# motherboard.net
KiCad netlist of a schematic drawn in EAGLE
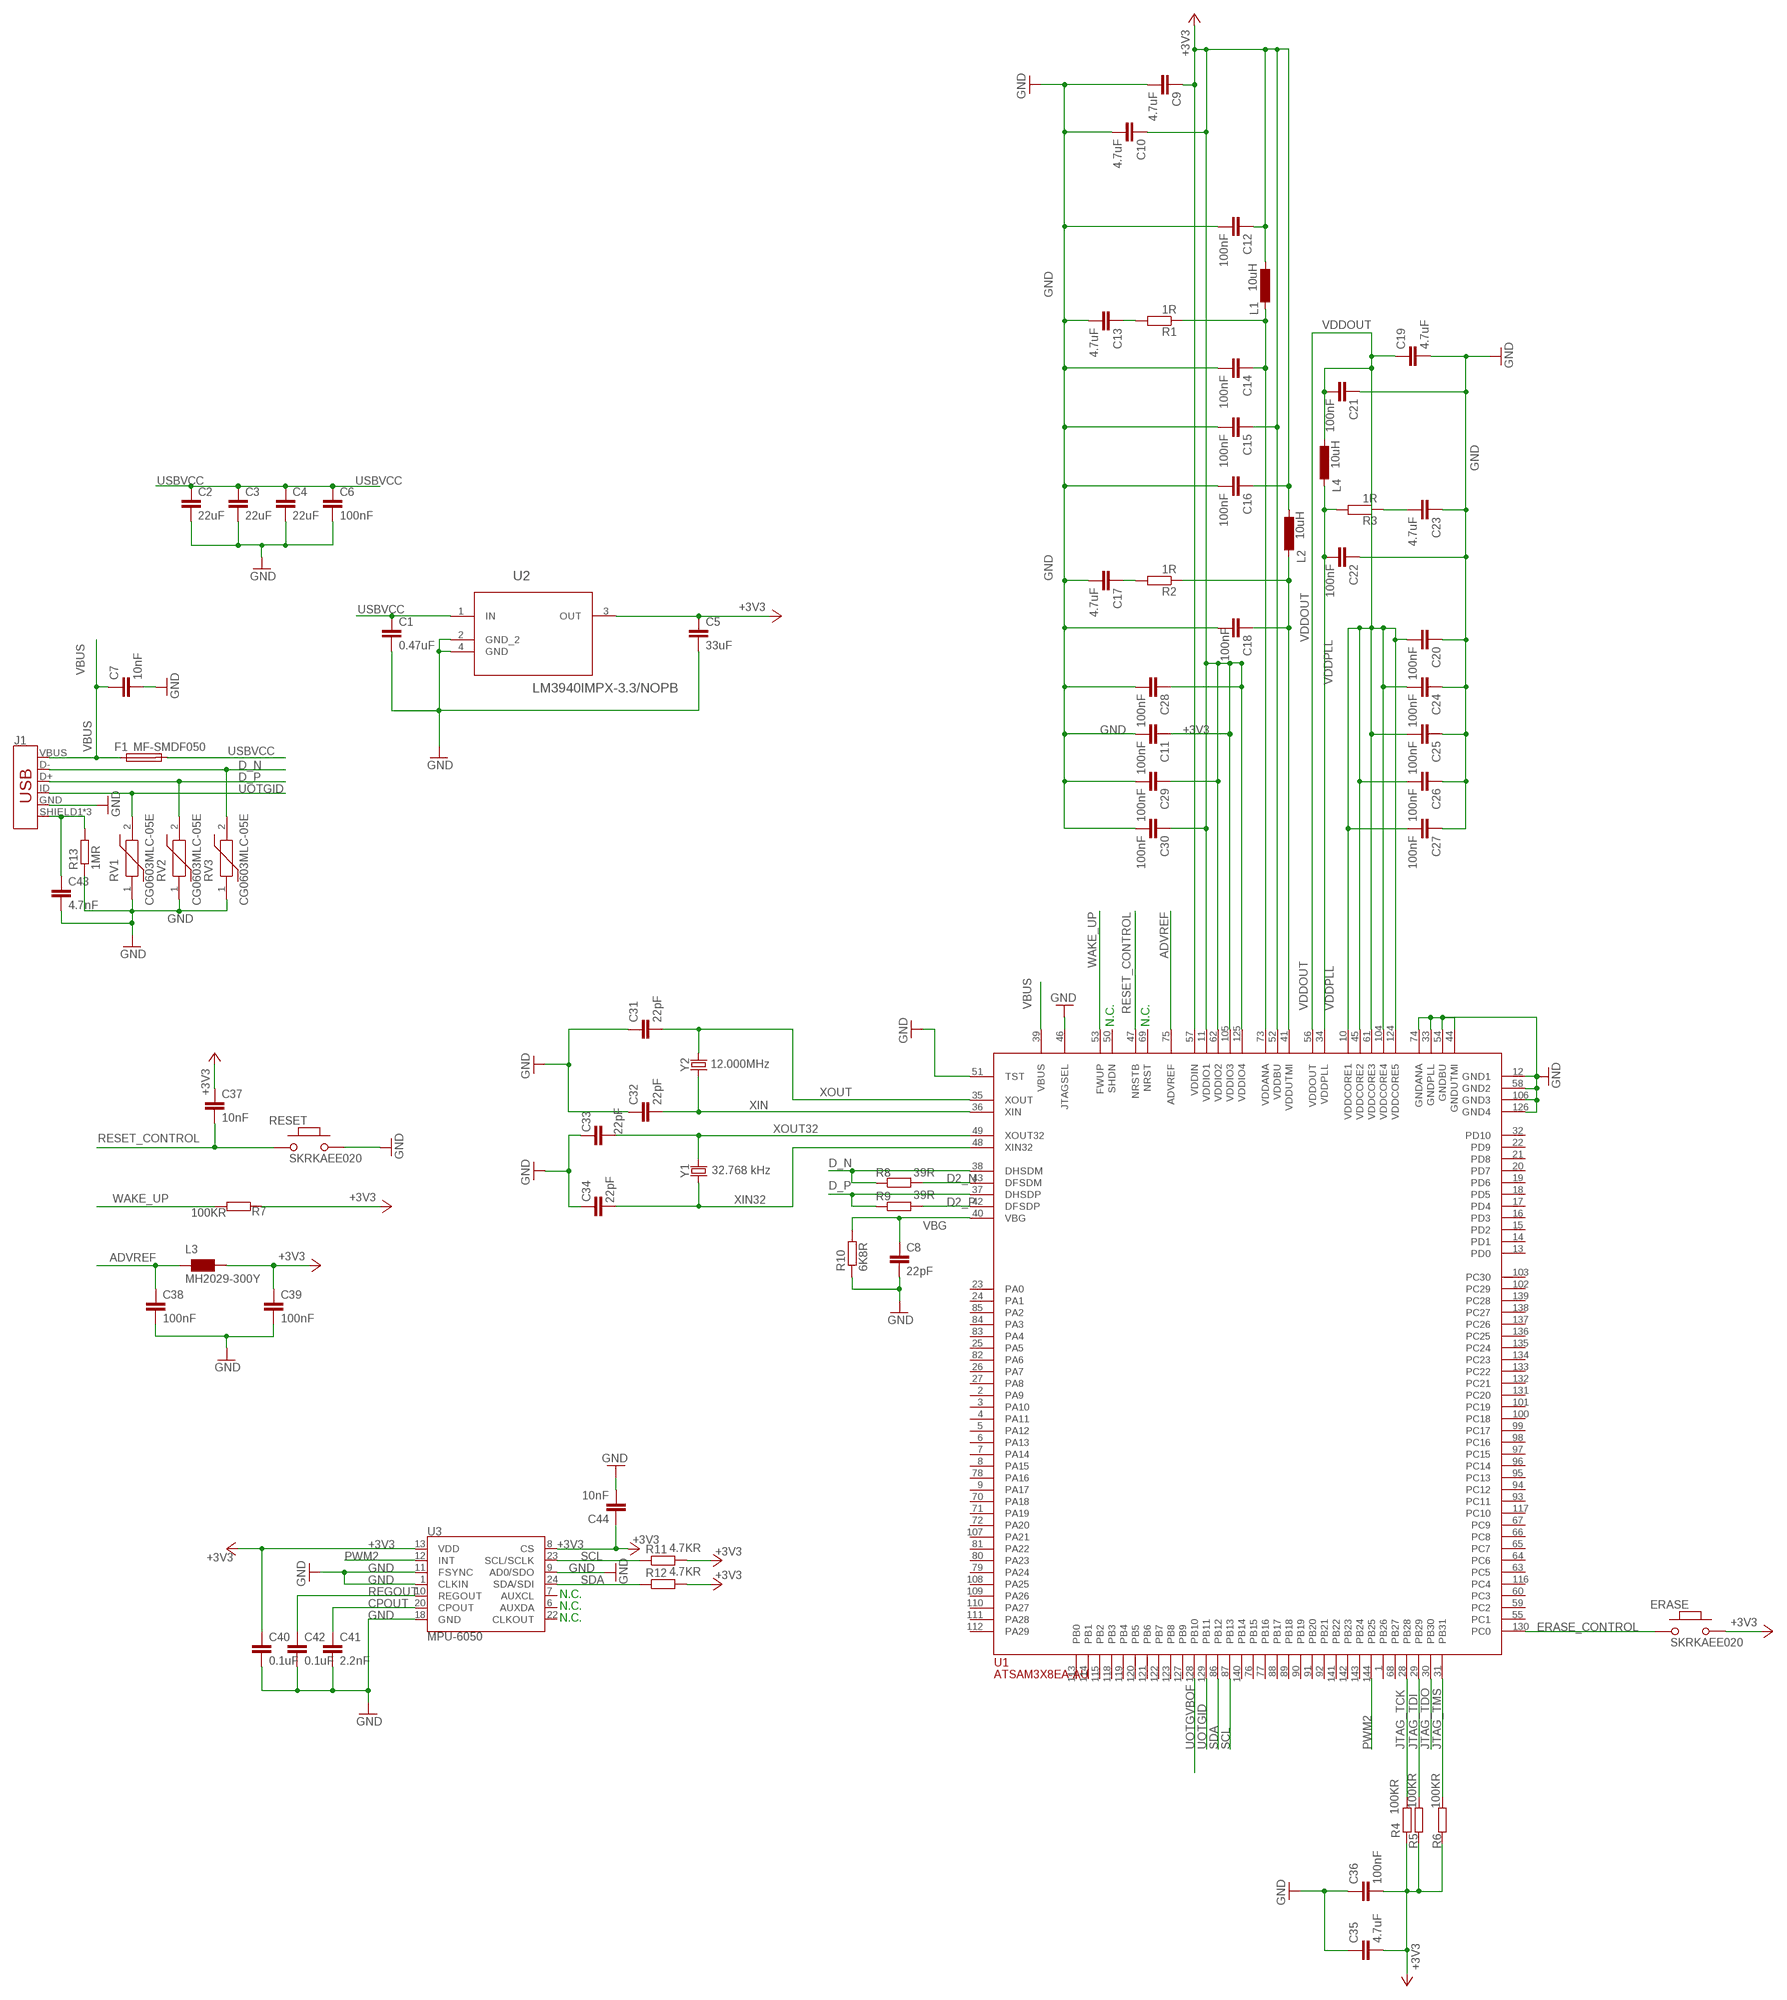
[diagram p0: schematic, sheet 1]

(export (version "E")
  (design (tool "Eeschema 10.0.6"))
  (components
    (comp (ref "C1")
      (value "0.47uF")
      (footprint "eagle-import:C0805")
      (libsource (lib "eagle-import") (part "C-EUC0805"))
    )
    (comp (ref "C2")
      (value "22uF")
      (footprint "eagle-import:C1206")
      (libsource (lib "eagle-import") (part "C-EUC1206"))
    )
    (comp (ref "C3")
      (value "22uF")
      (footprint "eagle-import:C1206")
      (libsource (lib "eagle-import") (part "C-EUC1206"))
    )
    (comp (ref "C4")
      (value "22uF")
      (footprint "eagle-import:C1206")
      (libsource (lib "eagle-import") (part "C-EUC1206"))
    )
    (comp (ref "C5")
      (value "33uF")
      (footprint "eagle-import:C1206")
      (libsource (lib "eagle-import") (part "C-EUC1206"))
    )
    (comp (ref "C6")
      (value "100nF")
      (footprint "eagle-import:C0402")
      (libsource (lib "eagle-import") (part "C-EUC0402"))
    )
    (comp (ref "C7")
      (value "10nF")
      (footprint "eagle-import:C0402")
      (libsource (lib "eagle-import") (part "C-EUC0402"))
    )
    (comp (ref "C8")
      (value "22pF")
      (footprint "eagle-import:C0402")
      (libsource (lib "eagle-import") (part "C-EUC0402"))
    )
    (comp (ref "C9")
      (value "4.7uF")
      (footprint "eagle-import:C0805")
      (libsource (lib "eagle-import") (part "C-EUC0805"))
    )
    (comp (ref "C10")
      (value "4.7uF")
      (footprint "eagle-import:C0805")
      (libsource (lib "eagle-import") (part "C-EUC0805"))
    )
    (comp (ref "C11")
      (value "100nF")
      (footprint "eagle-import:C0402")
      (libsource (lib "eagle-import") (part "C-EUC0402"))
    )
    (comp (ref "C12")
      (value "100nF")
      (footprint "eagle-import:C0402")
      (libsource (lib "eagle-import") (part "C-EUC0402"))
    )
    (comp (ref "C13")
      (value "4.7uF")
      (footprint "eagle-import:C0805")
      (libsource (lib "eagle-import") (part "C-EUC0805"))
    )
    (comp (ref "C14")
      (value "100nF")
      (footprint "eagle-import:C0402")
      (libsource (lib "eagle-import") (part "C-EUC0402"))
    )
    (comp (ref "C15")
      (value "100nF")
      (footprint "eagle-import:C0402")
      (libsource (lib "eagle-import") (part "C-EUC0402"))
    )
    (comp (ref "C16")
      (value "100nF")
      (footprint "eagle-import:C0402")
      (libsource (lib "eagle-import") (part "C-EUC0402"))
    )
    (comp (ref "C17")
      (value "4.7uF")
      (footprint "eagle-import:C0805")
      (libsource (lib "eagle-import") (part "C-EUC0805"))
    )
    (comp (ref "C18")
      (value "100nF")
      (footprint "eagle-import:C0201")
      (libsource (lib "eagle-import") (part "C-EUC0201"))
    )
    (comp (ref "C19")
      (value "4.7uF")
      (footprint "eagle-import:C0805")
      (libsource (lib "eagle-import") (part "C-EUC0805"))
    )
    (comp (ref "C20")
      (value "100nF")
      (footprint "eagle-import:C0402")
      (libsource (lib "eagle-import") (part "C-EUC0402"))
    )
    (comp (ref "C21")
      (value "100nF")
      (footprint "eagle-import:C0402")
      (libsource (lib "eagle-import") (part "C-EUC0402"))
    )
    (comp (ref "C22")
      (value "100nF")
      (footprint "eagle-import:C0402")
      (libsource (lib "eagle-import") (part "C-EUC0402"))
    )
    (comp (ref "C23")
      (value "4.7uF")
      (footprint "eagle-import:C0805")
      (libsource (lib "eagle-import") (part "C-EUC0805"))
    )
    (comp (ref "C24")
      (value "100nF")
      (footprint "eagle-import:C0402")
      (libsource (lib "eagle-import") (part "C-EUC0402"))
    )
    (comp (ref "C25")
      (value "100nF")
      (footprint "eagle-import:C0402")
      (libsource (lib "eagle-import") (part "C-EUC0402"))
    )
    (comp (ref "C26")
      (value "100nF")
      (footprint "eagle-import:C0402")
      (libsource (lib "eagle-import") (part "C-EUC0402"))
    )
    (comp (ref "C27")
      (value "100nF")
      (footprint "eagle-import:C0402")
      (libsource (lib "eagle-import") (part "C-EUC0402"))
    )
    (comp (ref "C28")
      (value "100nF")
      (footprint "eagle-import:C0402")
      (libsource (lib "eagle-import") (part "C-EUC0402"))
    )
    (comp (ref "C29")
      (value "100nF")
      (footprint "eagle-import:C0402")
      (libsource (lib "eagle-import") (part "C-EUC0402"))
    )
    (comp (ref "C30")
      (value "100nF")
      (footprint "eagle-import:C0402")
      (libsource (lib "eagle-import") (part "C-EUC0402"))
    )
    (comp (ref "C31")
      (value "22pF")
      (footprint "eagle-import:C0402")
      (libsource (lib "eagle-import") (part "C-EUC0402"))
    )
    (comp (ref "C32")
      (value "22pF")
      (footprint "eagle-import:C0402")
      (libsource (lib "eagle-import") (part "C-EUC0402"))
    )
    (comp (ref "C33")
      (value "22pF")
      (footprint "eagle-import:C0402")
      (libsource (lib "eagle-import") (part "C-EUC0402"))
    )
    (comp (ref "C34")
      (value "22pF")
      (footprint "eagle-import:C0402")
      (libsource (lib "eagle-import") (part "C-EUC0402"))
    )
    (comp (ref "C35")
      (value "4.7uF")
      (footprint "eagle-import:C0805")
      (libsource (lib "eagle-import") (part "C-EUC0805"))
    )
    (comp (ref "C36")
      (value "100nF")
      (footprint "eagle-import:C0402")
      (libsource (lib "eagle-import") (part "C-EUC0402"))
    )
    (comp (ref "C37")
      (value "10nF")
      (footprint "eagle-import:C0402")
      (libsource (lib "eagle-import") (part "C-EUC0402"))
    )
    (comp (ref "C38")
      (value "100nF")
      (footprint "eagle-import:C0402")
      (libsource (lib "eagle-import") (part "C-EUC0402"))
    )
    (comp (ref "C39")
      (value "100nF")
      (footprint "eagle-import:C0402")
      (libsource (lib "eagle-import") (part "C-EUC0402"))
    )
    (comp (ref "C40")
      (value "0.1uF")
      (footprint "eagle-import:C0402")
      (libsource (lib "eagle-import") (part "C-EUC0402"))
    )
    (comp (ref "C41")
      (value "2.2nF")
      (footprint "eagle-import:C0402")
      (libsource (lib "eagle-import") (part "C-EUC0402"))
    )
    (comp (ref "C42")
      (value "0.1uF")
      (footprint "eagle-import:C0402")
      (libsource (lib "eagle-import") (part "C-EUC0402"))
    )
    (comp (ref "C43")
      (value "4.7nF")
      (footprint "eagle-import:C0402")
      (libsource (lib "eagle-import") (part "C-EUC0402"))
    )
    (comp (ref "C44")
      (value "10nF")
      (footprint "eagle-import:C0402")
      (libsource (lib "eagle-import") (part "C-EUC0402"))
    )
    (comp (ref "ERASE")
      (value "SKRKAEE020")
      (footprint "eagle-import:SOD4829X200")
      (libsource (lib "eagle-import") (part "SKRKAEE020"))
    )
    (comp (ref "F1")
      (value "MF-SMDF050")
      (footprint "eagle-import:MF-SMDF050")
      (libsource (lib "eagle-import") (part "MF-SMDF050"))
    )
    (comp (ref "J1")
      (value "USB_MICRO-B_FEMALE-SMT")
      (footprint "eagle-import:USB-B-MICRO-SMD")
      (libsource (lib "eagle-import") (part "USB_MICRO-B_FEMALE-SMT"))
    )
    (comp (ref "L1")
      (value "10uH")
      (footprint "eagle-import:L2012C")
      (libsource (lib "eagle-import") (part "L-EUL2012C"))
    )
    (comp (ref "L2")
      (value "10uH")
      (footprint "eagle-import:L2012C")
      (libsource (lib "eagle-import") (part "L-EUL2012C"))
    )
    (comp (ref "L3")
      (value "MH2029-300Y")
      (footprint "eagle-import:2012-EU")
      (fields (field (name "PART_NUMBER") "BLM21PG300SN1D_/_MH2029-300Y"))
      (libsource (lib "eagle-import") (part "MH2029-300Y"))
    )
    (comp (ref "L4")
      (value "10uH")
      (footprint "eagle-import:L2012C")
      (libsource (lib "eagle-import") (part "L-EUL2012C"))
    )
    (comp (ref "R1")
      (value "1R")
      (footprint "eagle-import:R0402")
      (libsource (lib "eagle-import") (part "R-EU_R0402"))
    )
    (comp (ref "R2")
      (value "1R")
      (footprint "eagle-import:R0402")
      (libsource (lib "eagle-import") (part "R-EU_R0402"))
    )
    (comp (ref "R3")
      (value "1R")
      (footprint "eagle-import:R0402")
      (libsource (lib "eagle-import") (part "R-EU_R0402"))
    )
    (comp (ref "R4")
      (value "100KR")
      (footprint "eagle-import:R0603")
      (libsource (lib "eagle-import") (part "R-EU_R0603"))
    )
    (comp (ref "R5")
      (value "100KR")
      (footprint "eagle-import:R0603")
      (libsource (lib "eagle-import") (part "R-EU_R0603"))
    )
    (comp (ref "R6")
      (value "100KR")
      (footprint "eagle-import:R0603")
      (libsource (lib "eagle-import") (part "R-EU_R0603"))
    )
    (comp (ref "R7")
      (value "100KR")
      (footprint "eagle-import:R0603")
      (libsource (lib "eagle-import") (part "R-EU_R0603"))
    )
    (comp (ref "R8")
      (value "39R")
      (footprint "eagle-import:R0402")
      (libsource (lib "eagle-import") (part "R-EU_R0402"))
    )
    (comp (ref "R9")
      (value "39R")
      (footprint "eagle-import:R0402")
      (libsource (lib "eagle-import") (part "R-EU_R0402"))
    )
    (comp (ref "R10")
      (value "6K8R")
      (footprint "eagle-import:R2012")
      (libsource (lib "eagle-import") (part "R-EU_R2012"))
    )
    (comp (ref "R11")
      (value "4.7KR")
      (footprint "eagle-import:R0805")
      (libsource (lib "eagle-import") (part "R-EU_R0805"))
    )
    (comp (ref "R12")
      (value "4.7KR")
      (footprint "eagle-import:R0805")
      (libsource (lib "eagle-import") (part "R-EU_R0805"))
    )
    (comp (ref "R13")
      (value "1MR")
      (footprint "eagle-import:R1206")
      (libsource (lib "eagle-import") (part "R-EU_R1206"))
    )
    (comp (ref "RESET")
      (value "SKRKAEE020")
      (footprint "eagle-import:SOD4829X200")
      (libsource (lib "eagle-import") (part "SKRKAEE020"))
    )
    (comp (ref "RV1")
      (value "CG0603MLC-05E")
      (footprint "eagle-import:VARC1608X55N")
      (fields
        (field (name "MOUSER_PART_NUMBER") "652-CG0603MLC-05E")
        (field (name "RS_PART_NUMBER") "8518256")
      )
      (libsource (lib "eagle-import") (part "CG0603MLC-05E"))
    )
    (comp (ref "RV2")
      (value "CG0603MLC-05E")
      (footprint "eagle-import:VARC1608X55N")
      (fields
        (field (name "MOUSER_PART_NUMBER") "652-CG0603MLC-05E")
        (field (name "RS_PART_NUMBER") "8518256")
      )
      (libsource (lib "eagle-import") (part "CG0603MLC-05E"))
    )
    (comp (ref "RV3")
      (value "CG0603MLC-05E")
      (footprint "eagle-import:VARC1608X55N")
      (fields
        (field (name "MOUSER_PART_NUMBER") "652-CG0603MLC-05E")
        (field (name "RS_PART_NUMBER") "8518256")
      )
      (libsource (lib "eagle-import") (part "CG0603MLC-05E"))
    )
    (comp (ref "U1")
      (value "ATSAM3X8EA-AU")
      (footprint "eagle-import:LQFP144")
      (libsource (lib "eagle-import") (part "ATSAM3X8EA-AUAU"))
    )
    (comp (ref "U2")
      (value "LM3940IMPX-3.3/NOPB")
      (footprint "eagle-import:SOT230P696X180-4N")
      (fields (field (name "MF") "Texas Instruments"))
      (libsource (lib "eagle-import") (part "LM3940IMPX-3.3/NOPB"))
    )
    (comp (ref "U3")
      (value "MPU-6050")
      (footprint "eagle-import:QFN-24-EP")
      (libsource (lib "eagle-import") (part "MPU-6000"))
    )
    (comp (ref "Y1")
      (value "32.768 kHz")
      (footprint "eagle-import:CRYSTAL-SMD-3.2X1.5MM")
      (libsource (lib "eagle-import") (part "CRYSTALSMD-3.2X1.5"))
    )
    (comp (ref "Y2")
      (value "12.000MHz")
      (footprint "eagle-import:CRYSTAL-SMD-3.2X2.5MM")
      (libsource (lib "eagle-import") (part "CRYSTALSMD-3.2X2.5"))
    )
  )
  (nets
    (net (code "1") (name "+3V3") (class "Default")
      (node (ref "C10") (pin "1") (pinfunction "1_1") (pintype "passive"))
      (node (ref "C11") (pin "1") (pinfunction "1_1") (pintype "passive"))
      (node (ref "C12") (pin "1") (pinfunction "1_1") (pintype "passive"))
      (node (ref "C15") (pin "1") (pinfunction "1_1") (pintype "passive"))
      (node (ref "C16") (pin "1") (pinfunction "1_1") (pintype "passive"))
      (node (ref "C28") (pin "1") (pinfunction "1_1") (pintype "passive"))
      (node (ref "C29") (pin "1") (pinfunction "1_1") (pintype "passive"))
      (node (ref "C30") (pin "1") (pinfunction "1_1") (pintype "passive"))
      (node (ref "C35") (pin "2") (pinfunction "2_2") (pintype "passive"))
      (node (ref "C36") (pin "2") (pinfunction "2_2") (pintype "passive"))
      (node (ref "C37") (pin "1") (pinfunction "1_1") (pintype "passive"))
      (node (ref "C39") (pin "1") (pinfunction "1_1") (pintype "passive"))
      (node (ref "C40") (pin "1") (pinfunction "1_1") (pintype "passive"))
      (node (ref "C44") (pin "1") (pinfunction "1_1") (pintype "passive"))
      (node (ref "C5") (pin "1") (pinfunction "1_1") (pintype "passive"))
      (node (ref "C9") (pin "1") (pinfunction "1_1") (pintype "passive"))
      (node (ref "ERASE") (pin "2") (pinfunction "2_2") (pintype "passive"))
      (node (ref "L1") (pin "1") (pinfunction "1_1") (pintype "passive"))
      (node (ref "L2") (pin "1") (pinfunction "1_1") (pintype "passive"))
      (node (ref "L3") (pin "2") (pinfunction "2_2") (pintype "passive"))
      (node (ref "R11") (pin "2") (pinfunction "2_2") (pintype "passive"))
      (node (ref "R12") (pin "2") (pinfunction "2_2") (pintype "passive"))
      (node (ref "R4") (pin "1") (pinfunction "1_1") (pintype "passive"))
      (node (ref "R5") (pin "1") (pinfunction "1_1") (pintype "passive"))
      (node (ref "R6") (pin "1") (pinfunction "1_1") (pintype "passive"))
      (node (ref "R7") (pin "1") (pinfunction "1_1") (pintype "passive"))
      (node (ref "U1") (pin "105") (pinfunction "VDDIO3_105") (pintype "power_in"))
      (node (ref "U1") (pin "11") (pinfunction "VDDIO1_11") (pintype "power_in"))
      (node (ref "U1") (pin "125") (pinfunction "VDDIO4_125") (pintype "power_in"))
      (node (ref "U1") (pin "52") (pinfunction "VDDBU_52") (pintype "power_in"))
      (node (ref "U1") (pin "57") (pinfunction "VDDIN_57") (pintype "power_in"))
      (node (ref "U1") (pin "62") (pinfunction "VDDIO2_62") (pintype "power_in"))
      (node (ref "U2") (pin "3") (pinfunction "OUT_3") (pintype "output"))
      (node (ref "U3") (pin "13") (pinfunction "VDD_13") (pintype "bidirectional"))
      (node (ref "U3") (pin "8") (pinfunction "CS_8") (pintype "bidirectional"))
    )
    (net (code "2") (name "/ADVREF") (class "Default")
      (node (ref "C38") (pin "1") (pinfunction "1_1") (pintype "passive"))
      (node (ref "L3") (pin "1") (pinfunction "1_1") (pintype "passive"))
      (node (ref "U1") (pin "75") (pinfunction "ADVREF_75") (pintype "power_in"))
    )
    (net (code "3") (name "/CPOUT") (class "Default")
      (node (ref "C41") (pin "1") (pinfunction "1_1") (pintype "passive"))
      (node (ref "U3") (pin "20") (pinfunction "CPOUT_20") (pintype "bidirectional"))
    )
    (net (code "4") (name "/D2_N") (class "Default")
      (node (ref "R8") (pin "2") (pinfunction "2_2") (pintype "passive"))
      (node (ref "U1") (pin "43") (pinfunction "DFSDM_43") (pintype "input"))
    )
    (net (code "5") (name "/D2_P") (class "Default")
      (node (ref "R9") (pin "2") (pinfunction "2_2") (pintype "passive"))
      (node (ref "U1") (pin "42") (pinfunction "DFSDP_42") (pintype "input"))
    )
    (net (code "6") (name "/D_N") (class "Default")
      (node (ref "J1") (pin "D-") (pinfunction "D-_D-") (pintype "bidirectional"))
      (node (ref "R8") (pin "1") (pinfunction "1_1") (pintype "passive"))
      (node (ref "RV3") (pin "2") (pinfunction "2_2") (pintype "bidirectional"))
      (node (ref "U1") (pin "38") (pinfunction "DHSDM_38") (pintype "bidirectional"))
    )
    (net (code "7") (name "/D_P") (class "Default")
      (node (ref "J1") (pin "D+") (pinfunction "D+_D+") (pintype "bidirectional"))
      (node (ref "R9") (pin "1") (pinfunction "1_1") (pintype "passive"))
      (node (ref "RV2") (pin "2") (pinfunction "2_2") (pintype "bidirectional"))
      (node (ref "U1") (pin "37") (pinfunction "DHSDP_37") (pintype "bidirectional"))
    )
    (net (code "8") (name "/ERASE_CONTROL") (class "Default")
      (node (ref "ERASE") (pin "1") (pinfunction "1_1") (pintype "passive"))
      (node (ref "U1") (pin "130") (pinfunction "PC0_130") (pintype "bidirectional"))
    )
    (net (code "9") (name "/JTAG_TCK") (class "Default")
      (node (ref "R4") (pin "2") (pinfunction "2_2") (pintype "passive"))
      (node (ref "U1") (pin "28") (pinfunction "PB28_28") (pintype "bidirectional"))
    )
    (net (code "10") (name "/JTAG_TDI") (class "Default")
      (node (ref "R5") (pin "2") (pinfunction "2_2") (pintype "passive"))
      (node (ref "U1") (pin "29") (pinfunction "PB29_29") (pintype "bidirectional"))
    )
    (net (code "11") (name "/JTAG_TDO") (class "Default")
      (node (ref "U1") (pin "30") (pinfunction "PB30_30") (pintype "bidirectional"))
    )
    (net (code "12") (name "/JTAG_TMS") (class "Default")
      (node (ref "R6") (pin "2") (pinfunction "2_2") (pintype "passive"))
      (node (ref "U1") (pin "31") (pinfunction "PB31_31") (pintype "bidirectional"))
    )
    (net (code "13") (name "/PWM2") (class "Default")
      (node (ref "U1") (pin "144") (pinfunction "PB25_144") (pintype "bidirectional"))
      (node (ref "U3") (pin "12") (pinfunction "INT_12") (pintype "bidirectional"))
    )
    (net (code "14") (name "/REGOUT") (class "Default")
      (node (ref "C42") (pin "1") (pinfunction "1_1") (pintype "passive"))
      (node (ref "U3") (pin "10") (pinfunction "REGOUT_10") (pintype "bidirectional"))
    )
    (net (code "15") (name "/RESET_CONTROL") (class "Default")
      (node (ref "C37") (pin "2") (pinfunction "2_2") (pintype "passive"))
      (node (ref "RESET") (pin "1") (pinfunction "1_1") (pintype "passive"))
      (node (ref "U1") (pin "47") (pinfunction "NRSTB_47") (pintype "input"))
    )
    (net (code "16") (name "/SCL") (class "Default")
      (node (ref "R11") (pin "1") (pinfunction "1_1") (pintype "passive"))
      (node (ref "U1") (pin "87") (pinfunction "PB13_87") (pintype "bidirectional"))
      (node (ref "U3") (pin "23") (pinfunction "SCL/SCLK_23") (pintype "bidirectional"))
    )
    (net (code "17") (name "/SDA") (class "Default")
      (node (ref "R12") (pin "1") (pinfunction "1_1") (pintype "passive"))
      (node (ref "U1") (pin "86") (pinfunction "PB12_86") (pintype "bidirectional"))
      (node (ref "U3") (pin "24") (pinfunction "SDA/SDI_24") (pintype "bidirectional"))
    )
    (net (code "18") (name "/UOTGID") (class "Default")
      (node (ref "J1") (pin "ID") (pinfunction "ID_ID") (pintype "bidirectional"))
      (node (ref "RV1") (pin "2") (pinfunction "2_2") (pintype "bidirectional"))
      (node (ref "U1") (pin "129") (pinfunction "PB11_129") (pintype "bidirectional"))
    )
    (net (code "19") (name "/UOTGVBOF") (class "Default")
      (node (ref "U1") (pin "128") (pinfunction "PB10_128") (pintype "bidirectional"))
    )
    (net (code "20") (name "/USBVCC") (class "Default")
      (node (ref "C1") (pin "1") (pinfunction "1_1") (pintype "passive"))
      (node (ref "C2") (pin "1") (pinfunction "1_1") (pintype "passive"))
      (node (ref "C3") (pin "1") (pinfunction "1_1") (pintype "passive"))
      (node (ref "C4") (pin "1") (pinfunction "1_1") (pintype "passive"))
      (node (ref "C6") (pin "1") (pinfunction "1_1") (pintype "passive"))
      (node (ref "F1") (pin "2") (pinfunction "2_2") (pintype "passive"))
      (node (ref "U2") (pin "1") (pinfunction "IN_1") (pintype "power_in"))
    )
    (net (code "21") (name "/VBG") (class "Default")
      (node (ref "C8") (pin "1") (pinfunction "1_1") (pintype "passive"))
      (node (ref "R10") (pin "2") (pinfunction "2_2") (pintype "passive"))
      (node (ref "U1") (pin "40") (pinfunction "VBG_40") (pintype "passive"))
    )
    (net (code "22") (name "/VBUS") (class "Default")
      (node (ref "C7") (pin "1") (pinfunction "1_1") (pintype "passive"))
      (node (ref "F1") (pin "1") (pinfunction "1_1") (pintype "passive"))
      (node (ref "J1") (pin "VBUS") (pinfunction "VBUS_VBUS") (pintype "power_in"))
      (node (ref "U1") (pin "39") (pinfunction "VBUS_39") (pintype "power_in"))
    )
    (net (code "23") (name "/VDDOUT") (class "Default")
      (node (ref "C19") (pin "1") (pinfunction "1_1") (pintype "passive"))
      (node (ref "C20") (pin "2") (pinfunction "2_2") (pintype "passive"))
      (node (ref "C21") (pin "2") (pinfunction "2_2") (pintype "passive"))
      (node (ref "C24") (pin "2") (pinfunction "2_2") (pintype "passive"))
      (node (ref "C25") (pin "2") (pinfunction "2_2") (pintype "passive"))
      (node (ref "C26") (pin "2") (pinfunction "2_2") (pintype "passive"))
      (node (ref "C27") (pin "2") (pinfunction "2_2") (pintype "passive"))
      (node (ref "L4") (pin "1") (pinfunction "1_1") (pintype "passive"))
      (node (ref "U1") (pin "10") (pinfunction "VDDCORE1_10") (pintype "input"))
      (node (ref "U1") (pin "104") (pinfunction "VDDCORE4_104") (pintype "input"))
      (node (ref "U1") (pin "124") (pinfunction "VDDCORE5_124") (pintype "input"))
      (node (ref "U1") (pin "45") (pinfunction "VDDCORE2_45") (pintype "input"))
      (node (ref "U1") (pin "56") (pinfunction "VDDOUT_56") (pintype "output"))
      (node (ref "U1") (pin "61") (pinfunction "VDDCORE3_61") (pintype "input"))
    )
    (net (code "24") (name "/VDDPLL") (class "Default")
      (node (ref "C22") (pin "2") (pinfunction "2_2") (pintype "passive"))
      (node (ref "L4") (pin "2") (pinfunction "2_2") (pintype "passive"))
      (node (ref "R3") (pin "2") (pinfunction "2_2") (pintype "passive"))
      (node (ref "U1") (pin "34") (pinfunction "VDDPLL_34") (pintype "input"))
    )
    (net (code "25") (name "/WAKE_UP") (class "Default")
      (node (ref "R7") (pin "2") (pinfunction "2_2") (pintype "passive"))
      (node (ref "U1") (pin "53") (pinfunction "FWUP_53") (pintype "input"))
    )
    (net (code "26") (name "/XIN") (class "Default")
      (node (ref "C32") (pin "2") (pinfunction "2_2") (pintype "passive"))
      (node (ref "U1") (pin "36") (pinfunction "XIN_36") (pintype "input"))
      (node (ref "Y2") (pin "1") (pinfunction "1_1") (pintype "passive"))
    )
    (net (code "27") (name "/XIN32") (class "Default")
      (node (ref "C34") (pin "2") (pinfunction "2_2") (pintype "passive"))
      (node (ref "U1") (pin "48") (pinfunction "XIN32_48") (pintype "output"))
      (node (ref "Y1") (pin "P$1") (pinfunction "1_P$1") (pintype "passive"))
    )
    (net (code "28") (name "/XOUT") (class "Default")
      (node (ref "C31") (pin "2") (pinfunction "2_2") (pintype "passive"))
      (node (ref "U1") (pin "35") (pinfunction "XOUT_35") (pintype "output"))
      (node (ref "Y2") (pin "3") (pinfunction "2_3") (pintype "passive"))
    )
    (net (code "29") (name "/XOUT32") (class "Default")
      (node (ref "C33") (pin "2") (pinfunction "2_2") (pintype "passive"))
      (node (ref "U1") (pin "49") (pinfunction "XOUT32_49") (pintype "output"))
      (node (ref "Y1") (pin "P$2") (pinfunction "2_P$2") (pintype "passive"))
    )
    (net (code "30") (name "GND") (class "Default")
      (node (ref "C1") (pin "2") (pinfunction "2_2") (pintype "passive"))
      (node (ref "C10") (pin "2") (pinfunction "2_2") (pintype "passive"))
      (node (ref "C11") (pin "2") (pinfunction "2_2") (pintype "passive"))
      (node (ref "C12") (pin "2") (pinfunction "2_2") (pintype "passive"))
      (node (ref "C13") (pin "2") (pinfunction "2_2") (pintype "passive"))
      (node (ref "C14") (pin "2") (pinfunction "2_2") (pintype "passive"))
      (node (ref "C15") (pin "2") (pinfunction "2_2") (pintype "passive"))
      (node (ref "C16") (pin "2") (pinfunction "2_2") (pintype "passive"))
      (node (ref "C17") (pin "2") (pinfunction "2_2") (pintype "passive"))
      (node (ref "C18") (pin "2") (pinfunction "2_2") (pintype "passive"))
      (node (ref "C19") (pin "2") (pinfunction "2_2") (pintype "passive"))
      (node (ref "C2") (pin "2") (pinfunction "2_2") (pintype "passive"))
      (node (ref "C20") (pin "1") (pinfunction "1_1") (pintype "passive"))
      (node (ref "C21") (pin "1") (pinfunction "1_1") (pintype "passive"))
      (node (ref "C22") (pin "1") (pinfunction "1_1") (pintype "passive"))
      (node (ref "C23") (pin "1") (pinfunction "1_1") (pintype "passive"))
      (node (ref "C24") (pin "1") (pinfunction "1_1") (pintype "passive"))
      (node (ref "C25") (pin "1") (pinfunction "1_1") (pintype "passive"))
      (node (ref "C26") (pin "1") (pinfunction "1_1") (pintype "passive"))
      (node (ref "C27") (pin "1") (pinfunction "1_1") (pintype "passive"))
      (node (ref "C28") (pin "2") (pinfunction "2_2") (pintype "passive"))
      (node (ref "C29") (pin "2") (pinfunction "2_2") (pintype "passive"))
      (node (ref "C3") (pin "2") (pinfunction "2_2") (pintype "passive"))
      (node (ref "C30") (pin "2") (pinfunction "2_2") (pintype "passive"))
      (node (ref "C31") (pin "1") (pinfunction "1_1") (pintype "passive"))
      (node (ref "C32") (pin "1") (pinfunction "1_1") (pintype "passive"))
      (node (ref "C33") (pin "1") (pinfunction "1_1") (pintype "passive"))
      (node (ref "C34") (pin "1") (pinfunction "1_1") (pintype "passive"))
      (node (ref "C35") (pin "1") (pinfunction "1_1") (pintype "passive"))
      (node (ref "C36") (pin "1") (pinfunction "1_1") (pintype "passive"))
      (node (ref "C38") (pin "2") (pinfunction "2_2") (pintype "passive"))
      (node (ref "C39") (pin "2") (pinfunction "2_2") (pintype "passive"))
      (node (ref "C4") (pin "2") (pinfunction "2_2") (pintype "passive"))
      (node (ref "C40") (pin "2") (pinfunction "2_2") (pintype "passive"))
      (node (ref "C41") (pin "2") (pinfunction "2_2") (pintype "passive"))
      (node (ref "C42") (pin "2") (pinfunction "2_2") (pintype "passive"))
      (node (ref "C43") (pin "2") (pinfunction "2_2") (pintype "passive"))
      (node (ref "C44") (pin "2") (pinfunction "2_2") (pintype "passive"))
      (node (ref "C5") (pin "2") (pinfunction "2_2") (pintype "passive"))
      (node (ref "C6") (pin "2") (pinfunction "2_2") (pintype "passive"))
      (node (ref "C7") (pin "2") (pinfunction "2_2") (pintype "passive"))
      (node (ref "C8") (pin "2") (pinfunction "2_2") (pintype "passive"))
      (node (ref "C9") (pin "2") (pinfunction "2_2") (pintype "passive"))
      (node (ref "J1") (pin "GND") (pinfunction "GND_GND") (pintype "power_in"))
      (node (ref "R10") (pin "1") (pinfunction "1_1") (pintype "passive"))
      (node (ref "R13") (pin "1") (pinfunction "1_1") (pintype "passive"))
      (node (ref "RESET") (pin "2") (pinfunction "2_2") (pintype "passive"))
      (node (ref "RV1") (pin "1") (pinfunction "1_1") (pintype "bidirectional"))
      (node (ref "RV2") (pin "1") (pinfunction "1_1") (pintype "bidirectional"))
      (node (ref "RV3") (pin "1") (pinfunction "1_1") (pintype "bidirectional"))
      (node (ref "U1") (pin "106") (pinfunction "GND3_106") (pintype "power_in"))
      (node (ref "U1") (pin "12") (pinfunction "GND1_12") (pintype "power_in"))
      (node (ref "U1") (pin "126") (pinfunction "GND4_126") (pintype "power_in"))
      (node (ref "U1") (pin "33") (pinfunction "GNDPLL_33") (pintype "power_in"))
      (node (ref "U1") (pin "44") (pinfunction "GNDUTMI_44") (pintype "power_in"))
      (node (ref "U1") (pin "46") (pinfunction "JTAGSEL_46") (pintype "input"))
      (node (ref "U1") (pin "51") (pinfunction "TST_51") (pintype "input"))
      (node (ref "U1") (pin "54") (pinfunction "GNDBU_54") (pintype "power_in"))
      (node (ref "U1") (pin "58") (pinfunction "GND2_58") (pintype "power_in"))
      (node (ref "U1") (pin "74") (pinfunction "GNDANA_74") (pintype "power_in"))
      (node (ref "U2") (pin "2") (pinfunction "GND_2_2") (pintype "passive"))
      (node (ref "U2") (pin "4") (pinfunction "GND_4") (pintype "passive"))
      (node (ref "U3") (pin "1") (pinfunction "CLKIN_1") (pintype "bidirectional"))
      (node (ref "U3") (pin "11") (pinfunction "FSYNC_11") (pintype "bidirectional"))
      (node (ref "U3") (pin "18") (pinfunction "GND_18") (pintype "bidirectional"))
      (node (ref "U3") (pin "9") (pinfunction "AD0/SDO_9") (pintype "bidirectional"))
    )
    (net (code "31") (name "Net-(C13-Pad1)") (class "Default")
      (node (ref "C13") (pin "1") (pinfunction "1_1") (pintype "passive"))
      (node (ref "R1") (pin "2") (pinfunction "2_2") (pintype "passive"))
    )
    (net (code "32") (name "Net-(C17-Pad1)") (class "Default")
      (node (ref "C17") (pin "1") (pinfunction "1_1") (pintype "passive"))
      (node (ref "R2") (pin "2") (pinfunction "2_2") (pintype "passive"))
    )
    (net (code "33") (name "Net-(C23-Pad2)") (class "Default")
      (node (ref "C23") (pin "2") (pinfunction "2_2") (pintype "passive"))
      (node (ref "R3") (pin "1") (pinfunction "1_1") (pintype "passive"))
    )
    (net (code "34") (name "Net-(C43-Pad1)") (class "Default")
      (node (ref "C43") (pin "1") (pinfunction "1_1") (pintype "passive"))
      (node (ref "J1") (pin "SHIELD1") (pinfunction "SHIELD_SHIELD1") (pintype "bidirectional"))
      (node (ref "J1") (pin "SHIELD2") (pinfunction "SHIELD_SHIELD2") (pintype "bidirectional"))
      (node (ref "J1") (pin "SHIELD3") (pinfunction "SHIELD_SHIELD3") (pintype "bidirectional"))
      (node (ref "R13") (pin "2") (pinfunction "2_2") (pintype "passive"))
    )
    (net (code "35") (name "Net-(U1-VDDANA)") (class "Default")
      (node (ref "C14") (pin "1") (pinfunction "1_1") (pintype "passive"))
      (node (ref "L1") (pin "2") (pinfunction "2_2") (pintype "passive"))
      (node (ref "R1") (pin "1") (pinfunction "1_1") (pintype "passive"))
      (node (ref "U1") (pin "73") (pinfunction "VDDANA_73") (pintype "power_in"))
    )
    (net (code "36") (name "Net-(U1-VDDUTMI)") (class "Default")
      (node (ref "C18") (pin "1") (pinfunction "1_1") (pintype "passive"))
      (node (ref "L2") (pin "2") (pinfunction "2_2") (pintype "passive"))
      (node (ref "R2") (pin "1") (pinfunction "1_1") (pintype "passive"))
      (node (ref "U1") (pin "41") (pinfunction "VDDUTMI_41") (pintype "input"))
    )
    (net (code "37") (name "unconnected-(U1-NRST-Pad69)") (class "Default")
      (node (ref "U1") (pin "69") (pinfunction "NRST_69") (pintype "bidirectional"))
    )
    (net (code "38") (name "unconnected-(U1-PA0-Pad23)") (class "Default")
      (node (ref "U1") (pin "23") (pinfunction "PA0_23") (pintype "bidirectional"))
    )
    (net (code "39") (name "unconnected-(U1-PA1-Pad24)") (class "Default")
      (node (ref "U1") (pin "24") (pinfunction "PA1_24") (pintype "bidirectional"))
    )
    (net (code "40") (name "unconnected-(U1-PA2-Pad85)") (class "Default")
      (node (ref "U1") (pin "85") (pinfunction "PA2_85") (pintype "bidirectional"))
    )
    (net (code "41") (name "unconnected-(U1-PA3-Pad84)") (class "Default")
      (node (ref "U1") (pin "84") (pinfunction "PA3_84") (pintype "bidirectional"))
    )
    (net (code "42") (name "unconnected-(U1-PA4-Pad83)") (class "Default")
      (node (ref "U1") (pin "83") (pinfunction "PA4_83") (pintype "bidirectional"))
    )
    (net (code "43") (name "unconnected-(U1-PA5-Pad25)") (class "Default")
      (node (ref "U1") (pin "25") (pinfunction "PA5_25") (pintype "bidirectional"))
    )
    (net (code "44") (name "unconnected-(U1-PA6-Pad82)") (class "Default")
      (node (ref "U1") (pin "82") (pinfunction "PA6_82") (pintype "bidirectional"))
    )
    (net (code "45") (name "unconnected-(U1-PA7-Pad26)") (class "Default")
      (node (ref "U1") (pin "26") (pinfunction "PA7_26") (pintype "bidirectional"))
    )
    (net (code "46") (name "unconnected-(U1-PA8-Pad27)") (class "Default")
      (node (ref "U1") (pin "27") (pinfunction "PA8_27") (pintype "bidirectional"))
    )
    (net (code "47") (name "unconnected-(U1-PA9-Pad2)") (class "Default")
      (node (ref "U1") (pin "2") (pinfunction "PA9_2") (pintype "bidirectional"))
    )
    (net (code "48") (name "unconnected-(U1-PA10-Pad3)") (class "Default")
      (node (ref "U1") (pin "3") (pinfunction "PA10_3") (pintype "bidirectional"))
    )
    (net (code "49") (name "unconnected-(U1-PA11-Pad4)") (class "Default")
      (node (ref "U1") (pin "4") (pinfunction "PA11_4") (pintype "bidirectional"))
    )
    (net (code "50") (name "unconnected-(U1-PA12-Pad5)") (class "Default")
      (node (ref "U1") (pin "5") (pinfunction "PA12_5") (pintype "bidirectional"))
    )
    (net (code "51") (name "unconnected-(U1-PA13-Pad6)") (class "Default")
      (node (ref "U1") (pin "6") (pinfunction "PA13_6") (pintype "bidirectional"))
    )
    (net (code "52") (name "unconnected-(U1-PA14-Pad7)") (class "Default")
      (node (ref "U1") (pin "7") (pinfunction "PA14_7") (pintype "bidirectional"))
    )
    (net (code "53") (name "unconnected-(U1-PA15-Pad8)") (class "Default")
      (node (ref "U1") (pin "8") (pinfunction "PA15_8") (pintype "bidirectional"))
    )
    (net (code "54") (name "unconnected-(U1-PA16-Pad78)") (class "Default")
      (node (ref "U1") (pin "78") (pinfunction "PA16_78") (pintype "bidirectional"))
    )
    (net (code "55") (name "unconnected-(U1-PA17-Pad9)") (class "Default")
      (node (ref "U1") (pin "9") (pinfunction "PA17_9") (pintype "bidirectional"))
    )
    (net (code "56") (name "unconnected-(U1-PA18-Pad70)") (class "Default")
      (node (ref "U1") (pin "70") (pinfunction "PA18_70") (pintype "bidirectional"))
    )
    (net (code "57") (name "unconnected-(U1-PA19-Pad71)") (class "Default")
      (node (ref "U1") (pin "71") (pinfunction "PA19_71") (pintype "bidirectional"))
    )
    (net (code "58") (name "unconnected-(U1-PA20-Pad72)") (class "Default")
      (node (ref "U1") (pin "72") (pinfunction "PA20_72") (pintype "bidirectional"))
    )
    (net (code "59") (name "unconnected-(U1-PA21-Pad107)") (class "Default")
      (node (ref "U1") (pin "107") (pinfunction "PA21_107") (pintype "bidirectional"))
    )
    (net (code "60") (name "unconnected-(U1-PA22-Pad81)") (class "Default")
      (node (ref "U1") (pin "81") (pinfunction "PA22_81") (pintype "bidirectional"))
    )
    (net (code "61") (name "unconnected-(U1-PA23-Pad80)") (class "Default")
      (node (ref "U1") (pin "80") (pinfunction "PA23_80") (pintype "bidirectional"))
    )
    (net (code "62") (name "unconnected-(U1-PA24-Pad79)") (class "Default")
      (node (ref "U1") (pin "79") (pinfunction "PA24_79") (pintype "bidirectional"))
    )
    (net (code "63") (name "unconnected-(U1-PA25-Pad108)") (class "Default")
      (node (ref "U1") (pin "108") (pinfunction "PA25_108") (pintype "bidirectional"))
    )
    (net (code "64") (name "unconnected-(U1-PA26-Pad109)") (class "Default")
      (node (ref "U1") (pin "109") (pinfunction "PA26_109") (pintype "bidirectional"))
    )
    (net (code "65") (name "unconnected-(U1-PA27-Pad110)") (class "Default")
      (node (ref "U1") (pin "110") (pinfunction "PA27_110") (pintype "bidirectional"))
    )
    (net (code "66") (name "unconnected-(U1-PA28-Pad111)") (class "Default")
      (node (ref "U1") (pin "111") (pinfunction "PA28_111") (pintype "bidirectional"))
    )
    (net (code "67") (name "unconnected-(U1-PA29-Pad112)") (class "Default")
      (node (ref "U1") (pin "112") (pinfunction "PA29_112") (pintype "bidirectional"))
    )
    (net (code "68") (name "unconnected-(U1-PB0-Pad113)") (class "Default")
      (node (ref "U1") (pin "113") (pinfunction "PB0_113") (pintype "bidirectional"))
    )
    (net (code "69") (name "unconnected-(U1-PB1-Pad114)") (class "Default")
      (node (ref "U1") (pin "114") (pinfunction "PB1_114") (pintype "bidirectional"))
    )
    (net (code "70") (name "unconnected-(U1-PB2-Pad115)") (class "Default")
      (node (ref "U1") (pin "115") (pinfunction "PB2_115") (pintype "bidirectional"))
    )
    (net (code "71") (name "unconnected-(U1-PB3-Pad118)") (class "Default")
      (node (ref "U1") (pin "118") (pinfunction "PB3_118") (pintype "bidirectional"))
    )
    (net (code "72") (name "unconnected-(U1-PB4-Pad119)") (class "Default")
      (node (ref "U1") (pin "119") (pinfunction "PB4_119") (pintype "bidirectional"))
    )
    (net (code "73") (name "unconnected-(U1-PB5-Pad120)") (class "Default")
      (node (ref "U1") (pin "120") (pinfunction "PB5_120") (pintype "bidirectional"))
    )
    (net (code "74") (name "unconnected-(U1-PB6-Pad121)") (class "Default")
      (node (ref "U1") (pin "121") (pinfunction "PB6_121") (pintype "bidirectional"))
    )
    (net (code "75") (name "unconnected-(U1-PB7-Pad122)") (class "Default")
      (node (ref "U1") (pin "122") (pinfunction "PB7_122") (pintype "bidirectional"))
    )
    (net (code "76") (name "unconnected-(U1-PB8-Pad123)") (class "Default")
      (node (ref "U1") (pin "123") (pinfunction "PB8_123") (pintype "bidirectional"))
    )
    (net (code "77") (name "unconnected-(U1-PB9-Pad127)") (class "Default")
      (node (ref "U1") (pin "127") (pinfunction "PB9_127") (pintype "bidirectional"))
    )
    (net (code "78") (name "unconnected-(U1-PB14-Pad140)") (class "Default")
      (node (ref "U1") (pin "140") (pinfunction "PB14_140") (pintype "bidirectional"))
    )
    (net (code "79") (name "unconnected-(U1-PB15-Pad76)") (class "Default")
      (node (ref "U1") (pin "76") (pinfunction "PB15_76") (pintype "bidirectional"))
    )
    (net (code "80") (name "unconnected-(U1-PB16-Pad77)") (class "Default")
      (node (ref "U1") (pin "77") (pinfunction "PB16_77") (pintype "bidirectional"))
    )
    (net (code "81") (name "unconnected-(U1-PB17-Pad88)") (class "Default")
      (node (ref "U1") (pin "88") (pinfunction "PB17_88") (pintype "bidirectional"))
    )
    (net (code "82") (name "unconnected-(U1-PB18-Pad89)") (class "Default")
      (node (ref "U1") (pin "89") (pinfunction "PB18_89") (pintype "bidirectional"))
    )
    (net (code "83") (name "unconnected-(U1-PB19-Pad90)") (class "Default")
      (node (ref "U1") (pin "90") (pinfunction "PB19_90") (pintype "bidirectional"))
    )
    (net (code "84") (name "unconnected-(U1-PB20-Pad91)") (class "Default")
      (node (ref "U1") (pin "91") (pinfunction "PB20_91") (pintype "bidirectional"))
    )
    (net (code "85") (name "unconnected-(U1-PB21-Pad92)") (class "Default")
      (node (ref "U1") (pin "92") (pinfunction "PB21_92") (pintype "bidirectional"))
    )
    (net (code "86") (name "unconnected-(U1-PB22-Pad141)") (class "Default")
      (node (ref "U1") (pin "141") (pinfunction "PB22_141") (pintype "bidirectional"))
    )
    (net (code "87") (name "unconnected-(U1-PB23-Pad142)") (class "Default")
      (node (ref "U1") (pin "142") (pinfunction "PB23_142") (pintype "bidirectional"))
    )
    (net (code "88") (name "unconnected-(U1-PB24-Pad143)") (class "Default")
      (node (ref "U1") (pin "143") (pinfunction "PB24_143") (pintype "bidirectional"))
    )
    (net (code "89") (name "unconnected-(U1-PB26-Pad1)") (class "Default")
      (node (ref "U1") (pin "1") (pinfunction "PB26_1") (pintype "bidirectional"))
    )
    (net (code "90") (name "unconnected-(U1-PB27-Pad68)") (class "Default")
      (node (ref "U1") (pin "68") (pinfunction "PB27_68") (pintype "bidirectional"))
    )
    (net (code "91") (name "unconnected-(U1-PC1-Pad55)") (class "Default")
      (node (ref "U1") (pin "55") (pinfunction "PC1_55") (pintype "bidirectional"))
    )
    (net (code "92") (name "unconnected-(U1-PC2-Pad59)") (class "Default")
      (node (ref "U1") (pin "59") (pinfunction "PC2_59") (pintype "bidirectional"))
    )
    (net (code "93") (name "unconnected-(U1-PC3-Pad60)") (class "Default")
      (node (ref "U1") (pin "60") (pinfunction "PC3_60") (pintype "bidirectional"))
    )
    (net (code "94") (name "unconnected-(U1-PC4-Pad116)") (class "Default")
      (node (ref "U1") (pin "116") (pinfunction "PC4_116") (pintype "bidirectional"))
    )
    (net (code "95") (name "unconnected-(U1-PC5-Pad63)") (class "Default")
      (node (ref "U1") (pin "63") (pinfunction "PC5_63") (pintype "bidirectional"))
    )
    (net (code "96") (name "unconnected-(U1-PC6-Pad64)") (class "Default")
      (node (ref "U1") (pin "64") (pinfunction "PC6_64") (pintype "bidirectional"))
    )
    (net (code "97") (name "unconnected-(U1-PC7-Pad65)") (class "Default")
      (node (ref "U1") (pin "65") (pinfunction "PC7_65") (pintype "bidirectional"))
    )
    (net (code "98") (name "unconnected-(U1-PC8-Pad66)") (class "Default")
      (node (ref "U1") (pin "66") (pinfunction "PC8_66") (pintype "bidirectional"))
    )
    (net (code "99") (name "unconnected-(U1-PC9-Pad67)") (class "Default")
      (node (ref "U1") (pin "67") (pinfunction "PC9_67") (pintype "bidirectional"))
    )
    (net (code "100") (name "unconnected-(U1-PC10-Pad117)") (class "Default")
      (node (ref "U1") (pin "117") (pinfunction "PC10_117") (pintype "bidirectional"))
    )
    (net (code "101") (name "unconnected-(U1-PC11-Pad93)") (class "Default")
      (node (ref "U1") (pin "93") (pinfunction "PC11_93") (pintype "bidirectional"))
    )
    (net (code "102") (name "unconnected-(U1-PC12-Pad94)") (class "Default")
      (node (ref "U1") (pin "94") (pinfunction "PC12_94") (pintype "bidirectional"))
    )
    (net (code "103") (name "unconnected-(U1-PC13-Pad95)") (class "Default")
      (node (ref "U1") (pin "95") (pinfunction "PC13_95") (pintype "bidirectional"))
    )
    (net (code "104") (name "unconnected-(U1-PC14-Pad96)") (class "Default")
      (node (ref "U1") (pin "96") (pinfunction "PC14_96") (pintype "bidirectional"))
    )
    (net (code "105") (name "unconnected-(U1-PC15-Pad97)") (class "Default")
      (node (ref "U1") (pin "97") (pinfunction "PC15_97") (pintype "bidirectional"))
    )
    (net (code "106") (name "unconnected-(U1-PC16-Pad98)") (class "Default")
      (node (ref "U1") (pin "98") (pinfunction "PC16_98") (pintype "bidirectional"))
    )
    (net (code "107") (name "unconnected-(U1-PC17-Pad99)") (class "Default")
      (node (ref "U1") (pin "99") (pinfunction "PC17_99") (pintype "bidirectional"))
    )
    (net (code "108") (name "unconnected-(U1-PC18-Pad100)") (class "Default")
      (node (ref "U1") (pin "100") (pinfunction "PC18_100") (pintype "bidirectional"))
    )
    (net (code "109") (name "unconnected-(U1-PC19-Pad101)") (class "Default")
      (node (ref "U1") (pin "101") (pinfunction "PC19_101") (pintype "bidirectional"))
    )
    (net (code "110") (name "unconnected-(U1-PC20-Pad131)") (class "Default")
      (node (ref "U1") (pin "131") (pinfunction "PC20_131") (pintype "bidirectional"))
    )
    (net (code "111") (name "unconnected-(U1-PC21-Pad132)") (class "Default")
      (node (ref "U1") (pin "132") (pinfunction "PC21_132") (pintype "bidirectional"))
    )
    (net (code "112") (name "unconnected-(U1-PC22-Pad133)") (class "Default")
      (node (ref "U1") (pin "133") (pinfunction "PC22_133") (pintype "bidirectional"))
    )
    (net (code "113") (name "unconnected-(U1-PC23-Pad134)") (class "Default")
      (node (ref "U1") (pin "134") (pinfunction "PC23_134") (pintype "bidirectional"))
    )
    (net (code "114") (name "unconnected-(U1-PC24-Pad135)") (class "Default")
      (node (ref "U1") (pin "135") (pinfunction "PC24_135") (pintype "bidirectional"))
    )
    (net (code "115") (name "unconnected-(U1-PC25-Pad136)") (class "Default")
      (node (ref "U1") (pin "136") (pinfunction "PC25_136") (pintype "bidirectional"))
    )
    (net (code "116") (name "unconnected-(U1-PC26-Pad137)") (class "Default")
      (node (ref "U1") (pin "137") (pinfunction "PC26_137") (pintype "bidirectional"))
    )
    (net (code "117") (name "unconnected-(U1-PC27-Pad138)") (class "Default")
      (node (ref "U1") (pin "138") (pinfunction "PC27_138") (pintype "bidirectional"))
    )
    (net (code "118") (name "unconnected-(U1-PC28-Pad139)") (class "Default")
      (node (ref "U1") (pin "139") (pinfunction "PC28_139") (pintype "bidirectional"))
    )
    (net (code "119") (name "unconnected-(U1-PC29-Pad102)") (class "Default")
      (node (ref "U1") (pin "102") (pinfunction "PC29_102") (pintype "bidirectional"))
    )
    (net (code "120") (name "unconnected-(U1-PC30-Pad103)") (class "Default")
      (node (ref "U1") (pin "103") (pinfunction "PC30_103") (pintype "bidirectional"))
    )
    (net (code "121") (name "unconnected-(U1-PD0-Pad13)") (class "Default")
      (node (ref "U1") (pin "13") (pinfunction "PD0_13") (pintype "bidirectional"))
    )
    (net (code "122") (name "unconnected-(U1-PD1-Pad14)") (class "Default")
      (node (ref "U1") (pin "14") (pinfunction "PD1_14") (pintype "bidirectional"))
    )
    (net (code "123") (name "unconnected-(U1-PD2-Pad15)") (class "Default")
      (node (ref "U1") (pin "15") (pinfunction "PD2_15") (pintype "bidirectional"))
    )
    (net (code "124") (name "unconnected-(U1-PD3-Pad16)") (class "Default")
      (node (ref "U1") (pin "16") (pinfunction "PD3_16") (pintype "bidirectional"))
    )
    (net (code "125") (name "unconnected-(U1-PD4-Pad17)") (class "Default")
      (node (ref "U1") (pin "17") (pinfunction "PD4_17") (pintype "bidirectional"))
    )
    (net (code "126") (name "unconnected-(U1-PD5-Pad18)") (class "Default")
      (node (ref "U1") (pin "18") (pinfunction "PD5_18") (pintype "bidirectional"))
    )
    (net (code "127") (name "unconnected-(U1-PD6-Pad19)") (class "Default")
      (node (ref "U1") (pin "19") (pinfunction "PD6_19") (pintype "bidirectional"))
    )
    (net (code "128") (name "unconnected-(U1-PD7-Pad20)") (class "Default")
      (node (ref "U1") (pin "20") (pinfunction "PD7_20") (pintype "bidirectional"))
    )
    (net (code "129") (name "unconnected-(U1-PD8-Pad21)") (class "Default")
      (node (ref "U1") (pin "21") (pinfunction "PD8_21") (pintype "bidirectional"))
    )
    (net (code "130") (name "unconnected-(U1-PD9-Pad22)") (class "Default")
      (node (ref "U1") (pin "22") (pinfunction "PD9_22") (pintype "bidirectional"))
    )
    (net (code "131") (name "unconnected-(U1-PD10-Pad32)") (class "Default")
      (node (ref "U1") (pin "32") (pinfunction "PD10_32") (pintype "bidirectional"))
    )
    (net (code "132") (name "unconnected-(U1-SHDN-Pad50)") (class "Default")
      (node (ref "U1") (pin "50") (pinfunction "SHDN_50") (pintype "output"))
    )
    (net (code "133") (name "unconnected-(U3-AUXCL-Pad7)") (class "Default")
      (node (ref "U3") (pin "7") (pinfunction "AUXCL_7") (pintype "bidirectional"))
    )
    (net (code "134") (name "unconnected-(U3-AUXDA-Pad6)") (class "Default")
      (node (ref "U3") (pin "6") (pinfunction "AUXDA_6") (pintype "bidirectional"))
    )
    (net (code "135") (name "unconnected-(U3-CLKOUT-Pad22)") (class "Default")
      (node (ref "U3") (pin "22") (pinfunction "CLKOUT_22") (pintype "bidirectional"))
    )
  )
)
